# Pan-tilt.net
KiCad netlist of a schematic drawn in Altium Designer
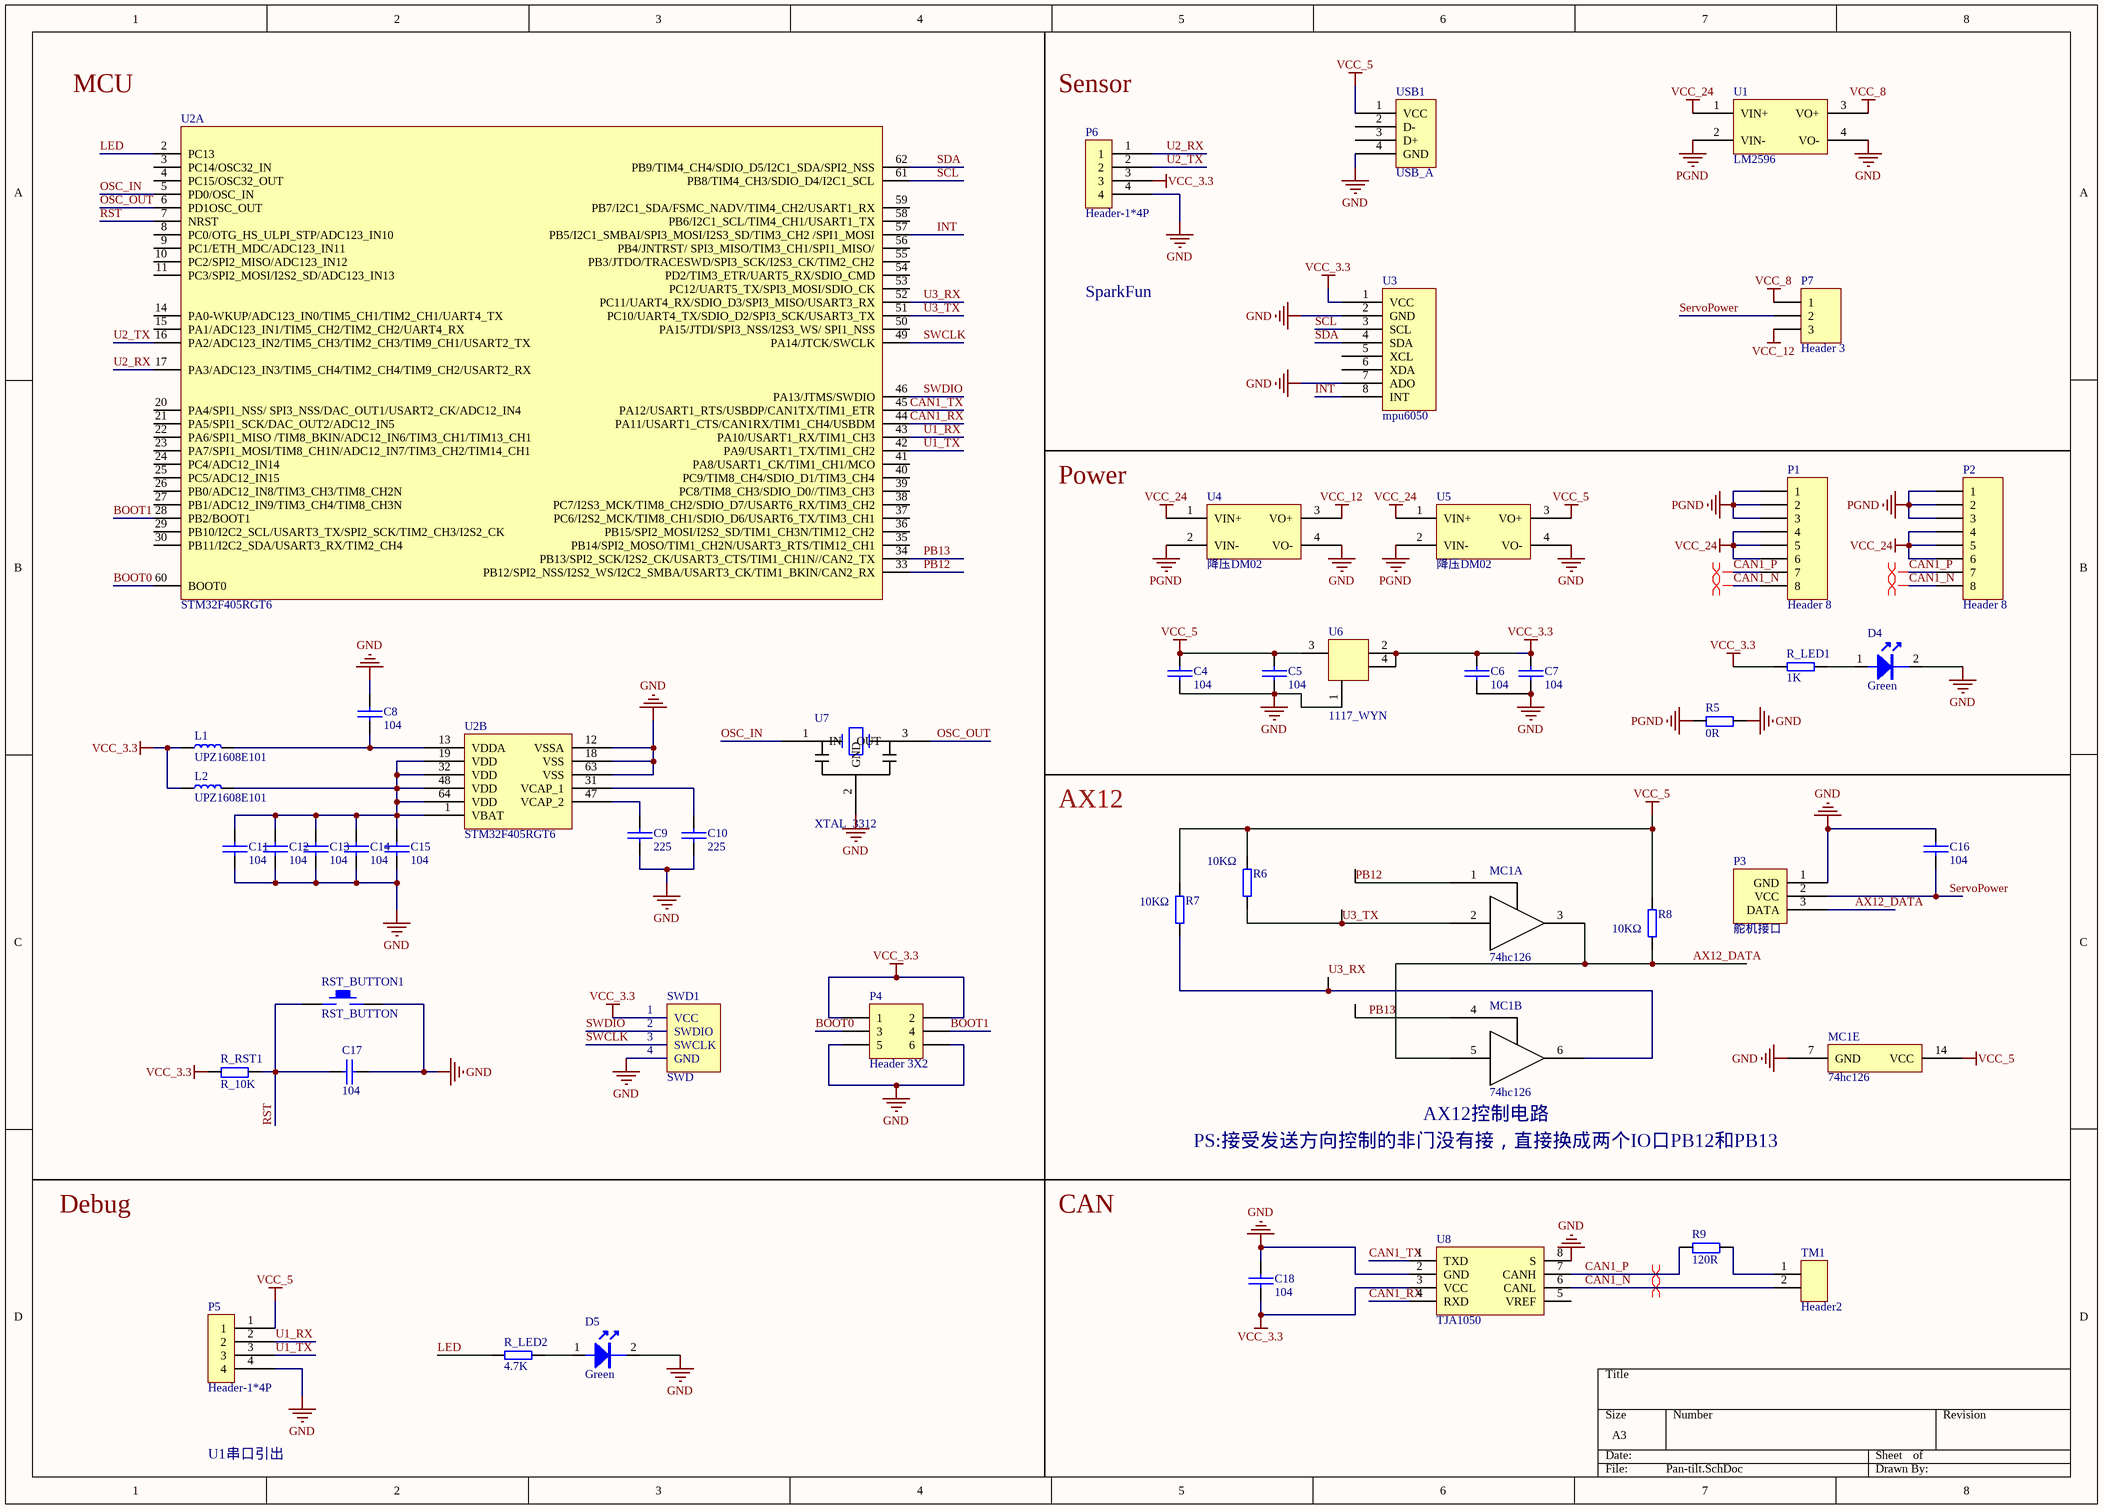
[diagram p0: Pan-tilt.SchDoc]

(export (version "E")
  (design (tool "Eeschema 10.0.6"))
  (components
    (comp (ref "C4") (value "104") (footprint "C0603/1608") (libsource (lib "PCB_Project") (part "CAP_WYN")))
    (comp (ref "C5") (value "104") (footprint "C0603/1608") (libsource (lib "PCB_Project") (part "CAP_WYN")))
    (comp (ref "C6") (value "104") (footprint "C0603/1608") (libsource (lib "PCB_Project") (part "CAP_WYN")))
    (comp (ref "C7") (value "104") (footprint "C0603/1608") (libsource (lib "PCB_Project") (part "CAP_WYN")))
    (comp (ref "C8") (value "104") (footprint "C0603/1608") (libsource (lib "RESCUE2019") (part "Capacitor")))
    (comp (ref "C9") (value "225") (footprint "C0603/1608") (libsource (lib "RESCUE2019") (part "Capacitor")))
    (comp (ref "C10")
      (value "225")
      (footprint "C0603/1608")
      (libsource (lib "RESCUE2019") (part "Capacitor"))
    )
    (comp (ref "C11")
      (value "104")
      (footprint "C0603/1608")
      (libsource (lib "RESCUE2019") (part "Capacitor"))
    )
    (comp (ref "C12")
      (value "104")
      (footprint "C0603/1608")
      (libsource (lib "RESCUE2019") (part "Capacitor"))
    )
    (comp (ref "C13")
      (value "104")
      (footprint "C0603/1608")
      (libsource (lib "RESCUE2019") (part "Capacitor"))
    )
    (comp (ref "C14")
      (value "104")
      (footprint "C0603/1608")
      (libsource (lib "RESCUE2019") (part "Capacitor"))
    )
    (comp (ref "C15")
      (value "104")
      (footprint "C0603/1608")
      (libsource (lib "RESCUE2019") (part "Capacitor"))
    )
    (comp (ref "C16") (value "104") (footprint "C0603/1608") (libsource (lib "PCB_Project") (part "CAP_WYN")))
    (comp (ref "C17")
      (value "104")
      (footprint "C0603/1608")
      (libsource (lib "RESCUE2019") (part "Capacitor"))
    )
    (comp (ref "C18") (value "104") (footprint "C0603/1608") (libsource (lib "PCB_Project") (part "CAP_WYN")))
    (comp (ref "D4")
      (value "LED Green")
      (footprint "LED0603-绿色")
      (fields (field (name "COLOR") "Green"))
      (libsource (lib "PCB_Project") (part "LED"))
    )
    (comp (ref "D5")
      (value "LED Green")
      (footprint "LED0603-绿色")
      (fields (field (name "COLOR") "Green"))
      (libsource (lib "PCB_Project") (part "LED"))
    )
    (comp (ref "L1")
      (value "UPZ1608E101")
      (footprint "L0603/1608")
      (description "贴片磁珠")
      (libsource (lib "RESCUE2019") (part "磁珠"))
    )
    (comp (ref "L2")
      (value "UPZ1608E101")
      (footprint "L0603/1608")
      (description "贴片磁珠")
      (libsource (lib "RESCUE2019") (part "磁珠"))
    )
    (comp (ref "MC1") (value "74hc126") (footprint "SOP-14") (libsource (lib "PCB_Project") (part "74hc126")))
    (comp (ref "P1")
      (value "Header 8")
      (footprint "XH2.54-8P（立式）")
      (description "Header, 8-Pin")
      (fields (field (name "PUBLISHER") "Altium Limited"))
      (libsource (lib "RESCUE2019") (part "Header 8"))
    )
    (comp (ref "P2")
      (value "Header 8")
      (footprint "XH2.54-8P（立式）")
      (description "Header, 8-Pin")
      (fields (field (name "PUBLISHER") "Altium Limited"))
      (libsource (lib "RESCUE2019") (part "Header 8"))
    )
    (comp (ref "P3")
      (value "舵机接口")
      (footprint "5263-3P（立式）")
      (libsource (lib "WMJ2019_Connectors") (part "舵机接口"))
    )
    (comp (ref "P4")
      (value "Header 3X2")
      (footprint "Header-2.54-2*3P（立式）")
      (description "Header, 3-Pin, Dual row")
      (fields (field (name "PUBLISHER") "Altium Limited"))
      (libsource (lib "RESCUE2019") (part "Header 3X2"))
    )
    (comp (ref "P5")
      (value "Header-1*4P")
      (footprint "XH2.54-4P（立式）")
      (description "单排4P排针")
      (libsource (lib "WMJ2019_Connectors") (part "Header-1*4P"))
    )
    (comp (ref "P6")
      (value "Header-1*4P")
      (footprint "XH2.54-4P（立式）")
      (description "单排4P排针")
      (libsource (lib "WMJ2019_Connectors") (part "Header-1*4P"))
    )
    (comp (ref "P7")
      (value "Header 3")
      (footprint "Header-2.54-1*3P（立式）")
      (description "Header, 3-Pin")
      (fields (field (name "PUBLISHER") "Altium Limited"))
      (libsource (lib "RESCUE2019") (part "Header 3"))
    )
    (comp (ref "R5") (value "0R") (footprint "R0603/1608") (libsource (lib "PCB_Project") (part "Resistor")))
    (comp (ref "R6") (value "10KΩ") (footprint "R0603/1608") (libsource (lib "main") (part "RES_WYN")))
    (comp (ref "R7") (value "10KΩ") (footprint "R0603/1608") (libsource (lib "main") (part "RES_WYN")))
    (comp (ref "R8") (value "10KΩ") (footprint "R0603/1608") (libsource (lib "main") (part "RES_WYN")))
    (comp (ref "R9")
      (value "120R")
      (footprint "R0603/1608")
      (libsource (lib "PCB_Project") (part "Resistor"))
    )
    (comp (ref "RST_BUTTON1")
      (value "RST_BUTTON")
      (footprint "SW-PB")
      (libsource (lib "PCB_Project") (part "RST_BUTTON"))
    )
    (comp (ref "R_LED1")
      (value "1K")
      (footprint "R0603/1608")
      (libsource (lib "PCB_Project") (part "RES_WYN"))
    )
    (comp (ref "R_LED2")
      (value "4.7K")
      (footprint "R0603/1608")
      (libsource (lib "PCB_Project") (part "RES_WYN"))
    )
    (comp (ref "R_RST1") (value "R_10K") (footprint "R0603/1608") (libsource (lib "PCB_Project") (part "R")))
    (comp (ref "SWD1") (value "SWD") (footprint "XH2.54-4P（立式）") (libsource (lib "RESCUE2019") (part "SWD")))
    (comp (ref "TM1")
      (value "Header2")
      (footprint "Header-2.54-1*2P（立式）")
      (libsource (lib "PCB_Project") (part "Header2"))
    )
    (comp (ref "U1") (value "LM2596") (footprint "LM2596_big") (libsource (lib "RESCUE2019") (part "降压DM02")))
    (comp (ref "U2")
      (value "STM32F405RGT6")
      (footprint "LQFP64")
      (description "微控制器STM32F405RGT6")
      (libsource (lib "RESCUE2019") (part "STM32F405RGT6"))
    )
    (comp (ref "U3")
      (value "mpu6050")
      (footprint "Header-2.54-1*8P（立式）")
      (libsource (lib "RESCUE2019") (part "mpu6050"))
    )
    (comp (ref "U4") (value "降压DM02") (footprint "DM02") (libsource (lib "PCB_Project") (part "降压DM02")))
    (comp (ref "U5") (value "降压DM02") (footprint "DM02") (libsource (lib "PCB_Project") (part "降压DM02")))
    (comp (ref "U6")
      (value "1117_WYN")
      (footprint "SOT-223")
      (libsource (lib "PCB_Project") (part "1117_WYN"))
    )
    (comp (ref "U7")
      (value "XTAL_3312")
      (footprint "XTAL-3213")
      (libsource (lib "RESCUE2019") (part "XTAL_3312"))
    )
    (comp (ref "U8") (value "TJA1050") (footprint "SOP-8") (libsource (lib "PCB_Project") (part "TJA1050")))
    (comp (ref "USB1")
      (value "USB_A")
      (footprint "USB_A Receptacle - 直插")
      (libsource (lib "RESCUE2019") (part "USB_A"))
    )
  )
  (nets
    (net (code "1") (name "/AX12_DATA") (class "Default")
      (node (ref "MC1") (pin "3") (pintype "passive"))
      (node (ref "MC1") (pin "5") (pintype "passive"))
      (node (ref "P3") (pin "3") (pinfunction "DATA_3") (pintype "passive"))
      (node (ref "R8") (pin "1") (pinfunction "1_1") (pintype "passive"))
    )
    (net (code "2") (name "/BOOT0") (class "Default")
      (node (ref "P4") (pin "3") (pinfunction "3_3") (pintype "passive"))
      (node (ref "U2") (pin "60") (pinfunction "BOOT0_60") (pintype "passive"))
    )
    (net (code "3") (name "/BOOT1") (class "Default")
      (node (ref "P4") (pin "4") (pinfunction "4_4") (pintype "passive"))
      (node (ref "U2") (pin "28") (pinfunction "PB2/BOOT1_28") (pintype "passive"))
    )
    (net (code "4") (name "/CAN1_N") (class "Default")
      (node (ref "P1") (pin "8") (pinfunction "8_8") (pintype "passive"))
      (node (ref "P2") (pin "8") (pinfunction "8_8") (pintype "passive"))
      (node (ref "TM1") (pin "2") (pintype "passive"))
      (node (ref "U8") (pin "6") (pinfunction "CANL_6") (pintype "passive"))
    )
    (net (code "5") (name "/CAN1_P") (class "Default")
      (node (ref "P1") (pin "7") (pinfunction "7_7") (pintype "passive"))
      (node (ref "P2") (pin "7") (pinfunction "7_7") (pintype "passive"))
      (node (ref "R9") (pin "1") (pintype "passive"))
      (node (ref "U8") (pin "7") (pinfunction "CANH_7") (pintype "passive"))
    )
    (net (code "6") (name "/CAN1_RX") (class "Default")
      (node (ref "U2") (pin "44") (pinfunction "PA11/USART1_CTS/CAN1RX/TIM1_CH4/USBDM_44") (pintype "passive"))
      (node (ref "U8") (pin "4") (pinfunction "RXD_4") (pintype "passive"))
    )
    (net (code "7") (name "/CAN1_TX") (class "Default")
      (node (ref "U2") (pin "45") (pinfunction "PA12/USART1_RTS/USBDP/CAN1TX/TIM1_ETR_45") (pintype "passive"))
      (node (ref "U8") (pin "1") (pinfunction "TXD_1") (pintype "passive"))
    )
    (net (code "8") (name "/INT") (class "Default")
      (node (ref "U2") (pin "57") (pinfunction "PB5/I2C1_SMBAI/SPI3_MOSI/I2S3_SD/TIM3_CH2_/SPI1_MOSI_57") (pintype "passive"))
      (node (ref "U3") (pin "8") (pinfunction "INT_8") (pintype "passive"))
    )
    (net (code "9") (name "/LED") (class "Default")
      (node (ref "R_LED2") (pin "1") (pinfunction "1_1") (pintype "passive"))
      (node (ref "U2") (pin "2") (pinfunction "PC13_2") (pintype "passive"))
    )
    (net (code "10") (name "/OSC_IN") (class "Default")
      (node (ref "U2") (pin "5") (pinfunction "PD0/OSC_IN_5") (pintype "passive"))
      (node (ref "U7") (pin "1") (pinfunction "IN_1") (pintype "passive"))
    )
    (net (code "11") (name "/OSC_OUT") (class "Default")
      (node (ref "U2") (pin "6") (pinfunction "PD1OSC_OUT_6") (pintype "passive"))
      (node (ref "U7") (pin "3") (pinfunction "OUT_3") (pintype "passive"))
    )
    (net (code "12") (name "/PB12") (class "Default")
      (node (ref "MC1") (pin "1") (pintype "input"))
      (node (ref "U2") (pin "33") (pinfunction "PB12/SPI2_NSS/I2S2_WS/I2C2_SMBA/USART3_CK/TIM1_BKIN/CAN2_RX_33") (pintype "passive"))
    )
    (net (code "13") (name "/PB13") (class "Default")
      (node (ref "MC1") (pin "4") (pintype "passive"))
      (node (ref "U2") (pin "34") (pinfunction "PB13/SPI2_SCK/I2S2_CK/USART3_CTS/TIM1_CH1N//CAN2_TX_34") (pintype "passive"))
    )
    (net (code "14") (name "/RST") (class "Default")
      (node (ref "C17") (pin "2") (pintype "passive"))
      (node (ref "RST_BUTTON1") (pin "1") (pinfunction "1_1") (pintype "passive"))
      (node (ref "R_RST1") (pin "2") (pintype "passive"))
      (node (ref "U2") (pin "7") (pinfunction "NRST_7") (pintype "passive"))
    )
    (net (code "15") (name "/SCL") (class "Default")
      (node (ref "U2") (pin "61") (pinfunction "PB8/TIM4_CH3/SDIO_D4/I2C1_SCL_61") (pintype "passive"))
      (node (ref "U3") (pin "3") (pinfunction "SCL_3") (pintype "passive"))
    )
    (net (code "16") (name "/SDA") (class "Default")
      (node (ref "U2") (pin "62") (pinfunction "PB9/TIM4_CH4/SDIO_D5/I2C1_SDA/SPI2_NSS_62") (pintype "passive"))
      (node (ref "U3") (pin "4") (pinfunction "SDA_4") (pintype "passive"))
    )
    (net (code "17") (name "/SWCLK") (class "Default")
      (node (ref "SWD1") (pin "3") (pinfunction "SWCLK_3") (pintype "passive"))
      (node (ref "U2") (pin "49") (pinfunction "PA14/JTCK/SWCLK_49") (pintype "passive"))
    )
    (net (code "18") (name "/SWDIO") (class "Default")
      (node (ref "SWD1") (pin "2") (pinfunction "SWDIO_2") (pintype "passive"))
      (node (ref "U2") (pin "46") (pinfunction "PA13/JTMS/SWDIO_46") (pintype "passive"))
    )
    (net (code "19") (name "/ServoPower") (class "Default")
      (node (ref "C16") (pin "2") (pintype "passive"))
      (node (ref "P3") (pin "2") (pinfunction "VCC_2") (pintype "passive"))
      (node (ref "P7") (pin "2") (pinfunction "2_2") (pintype "passive"))
    )
    (net (code "20") (name "/U1_RX") (class "Default")
      (node (ref "P5") (pin "2") (pinfunction "2_2") (pintype "passive"))
      (node (ref "U2") (pin "43") (pinfunction "PA10/USART1_RX/TIM1_CH3_43") (pintype "passive"))
    )
    (net (code "21") (name "/U1_TX") (class "Default")
      (node (ref "P5") (pin "3") (pinfunction "3_3") (pintype "passive"))
      (node (ref "U2") (pin "42") (pinfunction "PA9/USART1_TX/TIM1_CH2_42") (pintype "passive"))
    )
    (net (code "22") (name "/U2_RX") (class "Default")
      (node (ref "P6") (pin "1") (pinfunction "1_1") (pintype "passive"))
      (node (ref "U2") (pin "17") (pinfunction "PA3/ADC123_IN3/TIM5_CH4/TIM2_CH4/TIM9_CH2/USART2_RX_17") (pintype "passive"))
    )
    (net (code "23") (name "/U2_TX") (class "Default")
      (node (ref "P6") (pin "2") (pinfunction "2_2") (pintype "passive"))
      (node (ref "U2") (pin "16") (pinfunction "PA2/ADC123_IN2/TIM5_CH3/TIM2_CH3/TIM9_CH1/USART2_TX_16") (pintype "passive"))
    )
    (net (code "24") (name "/U3_RX") (class "Default")
      (node (ref "MC1") (pin "6") (pintype "passive"))
      (node (ref "R7") (pin "1") (pinfunction "1_1") (pintype "passive"))
      (node (ref "U2") (pin "52") (pinfunction "PC11/UART4_RX/SDIO_D3/SPI3_MISO/USART3_RX_52") (pintype "passive"))
    )
    (net (code "25") (name "/U3_TX") (class "Default")
      (node (ref "MC1") (pin "2") (pintype "input"))
      (node (ref "R6") (pin "1") (pinfunction "1_1") (pintype "passive"))
      (node (ref "U2") (pin "51") (pinfunction "PC10/UART4_TX/SDIO_D2/SPI3_SCK/USART3_TX_51") (pintype "passive"))
    )
    (net (code "26") (name "GND") (class "Default")
      (node (ref "C10") (pin "2") (pintype "passive"))
      (node (ref "C11") (pin "2") (pintype "passive"))
      (node (ref "C12") (pin "2") (pintype "passive"))
      (node (ref "C13") (pin "2") (pintype "passive"))
      (node (ref "C14") (pin "2") (pintype "passive"))
      (node (ref "C15") (pin "2") (pintype "passive"))
      (node (ref "C16") (pin "1") (pintype "passive"))
      (node (ref "C17") (pin "1") (pintype "passive"))
      (node (ref "C18") (pin "1") (pintype "passive"))
      (node (ref "C4") (pin "2") (pintype "passive"))
      (node (ref "C5") (pin "2") (pintype "passive"))
      (node (ref "C6") (pin "2") (pintype "passive"))
      (node (ref "C7") (pin "2") (pintype "passive"))
      (node (ref "C8") (pin "1") (pintype "passive"))
      (node (ref "C9") (pin "2") (pintype "passive"))
      (node (ref "D4") (pin "2") (pinfunction "K_2") (pintype "passive"))
      (node (ref "D5") (pin "2") (pinfunction "K_2") (pintype "passive"))
      (node (ref "MC1") (pin "7") (pinfunction "GND_7") (pintype "passive"))
      (node (ref "P3") (pin "1") (pinfunction "GND_1") (pintype "passive"))
      (node (ref "P4") (pin "5") (pinfunction "5_5") (pintype "passive"))
      (node (ref "P4") (pin "6") (pinfunction "6_6") (pintype "passive"))
      (node (ref "P5") (pin "4") (pinfunction "4_4") (pintype "passive"))
      (node (ref "P6") (pin "4") (pinfunction "4_4") (pintype "passive"))
      (node (ref "R5") (pin "2") (pintype "passive"))
      (node (ref "RST_BUTTON1") (pin "2") (pinfunction "2_2") (pintype "passive"))
      (node (ref "SWD1") (pin "4") (pinfunction "GND_4") (pintype "passive"))
      (node (ref "U1") (pin "4") (pinfunction "VO-_4") (pintype "passive"))
      (node (ref "U2") (pin "12") (pinfunction "VSSA_12") (pintype "passive"))
      (node (ref "U2") (pin "18") (pinfunction "VSS_18") (pintype "passive"))
      (node (ref "U2") (pin "63") (pinfunction "VSS_63") (pintype "passive"))
      (node (ref "U3") (pin "2") (pinfunction "GND_2") (pintype "passive"))
      (node (ref "U3") (pin "7") (pinfunction "ADO_7") (pintype "passive"))
      (node (ref "U4") (pin "4") (pinfunction "VO-_4") (pintype "passive"))
      (node (ref "U5") (pin "4") (pinfunction "VO-_4") (pintype "passive"))
      (node (ref "U6") (pin "1") (pintype "passive"))
      (node (ref "U7") (pin "2") (pinfunction "GND_2") (pintype "passive"))
      (node (ref "U8") (pin "2") (pinfunction "GND_2") (pintype "passive"))
      (node (ref "U8") (pin "8") (pinfunction "S_8") (pintype "passive"))
      (node (ref "USB1") (pin "4") (pinfunction "GND_4") (pintype "passive"))
    )
    (net (code "27") (name "Net-(D4-A)") (class "Default")
      (node (ref "D4") (pin "1") (pinfunction "A_1") (pintype "passive"))
      (node (ref "R_LED1") (pin "2") (pinfunction "2_2") (pintype "passive"))
    )
    (net (code "28") (name "Net-(D5-A)") (class "Default")
      (node (ref "D5") (pin "1") (pinfunction "A_1") (pintype "passive"))
      (node (ref "R_LED2") (pin "2") (pinfunction "2_2") (pintype "passive"))
    )
    (net (code "29") (name "Net-(R9-Pad2)") (class "Default")
      (node (ref "R9") (pin "2") (pintype "passive"))
      (node (ref "TM1") (pin "1") (pintype "passive"))
    )
    (net (code "30") (name "Net-(U2B-VBAT)") (class "Default")
      (node (ref "C11") (pin "1") (pintype "passive"))
      (node (ref "C12") (pin "1") (pintype "passive"))
      (node (ref "C13") (pin "1") (pintype "passive"))
      (node (ref "C14") (pin "1") (pintype "passive"))
      (node (ref "C15") (pin "1") (pintype "passive"))
      (node (ref "L2") (pin "2") (pinfunction "2_2") (pintype "passive"))
      (node (ref "U2") (pin "1") (pinfunction "VBAT_1") (pintype "passive"))
      (node (ref "U2") (pin "19") (pinfunction "VDD_19") (pintype "passive"))
      (node (ref "U2") (pin "32") (pinfunction "VDD_32") (pintype "passive"))
      (node (ref "U2") (pin "48") (pinfunction "VDD_48") (pintype "passive"))
      (node (ref "U2") (pin "64") (pinfunction "VDD_64") (pintype "passive"))
    )
    (net (code "31") (name "Net-(U2B-VCAP_1)") (class "Default")
      (node (ref "C10") (pin "1") (pintype "passive"))
      (node (ref "U2") (pin "31") (pinfunction "VCAP_1_31") (pintype "passive"))
    )
    (net (code "32") (name "Net-(U2B-VCAP_2)") (class "Default")
      (node (ref "C9") (pin "1") (pintype "passive"))
      (node (ref "U2") (pin "47") (pinfunction "VCAP_2_47") (pintype "passive"))
    )
    (net (code "33") (name "Net-(U2B-VDDA)") (class "Default")
      (node (ref "C8") (pin "2") (pintype "passive"))
      (node (ref "L1") (pin "2") (pinfunction "2_2") (pintype "passive"))
      (node (ref "U2") (pin "13") (pinfunction "VDDA_13") (pintype "passive"))
    )
    (net (code "34") (name "PGND") (class "Default")
      (node (ref "P1") (pin "1") (pinfunction "1_1") (pintype "passive"))
      (node (ref "P1") (pin "2") (pinfunction "2_2") (pintype "passive"))
      (node (ref "P1") (pin "3") (pinfunction "3_3") (pintype "passive"))
      (node (ref "P2") (pin "1") (pinfunction "1_1") (pintype "passive"))
      (node (ref "P2") (pin "2") (pinfunction "2_2") (pintype "passive"))
      (node (ref "P2") (pin "3") (pinfunction "3_3") (pintype "passive"))
      (node (ref "R5") (pin "1") (pintype "passive"))
      (node (ref "U1") (pin "2") (pinfunction "VIN-_2") (pintype "passive"))
      (node (ref "U4") (pin "2") (pinfunction "VIN-_2") (pintype "passive"))
      (node (ref "U5") (pin "2") (pinfunction "VIN-_2") (pintype "passive"))
    )
    (net (code "35") (name "VCC_3.3") (class "Default")
      (node (ref "C18") (pin "2") (pintype "passive"))
      (node (ref "C6") (pin "1") (pintype "passive"))
      (node (ref "C7") (pin "1") (pintype "passive"))
      (node (ref "L1") (pin "1") (pinfunction "1_1") (pintype "passive"))
      (node (ref "L2") (pin "1") (pinfunction "1_1") (pintype "passive"))
      (node (ref "P4") (pin "1") (pinfunction "1_1") (pintype "passive"))
      (node (ref "P4") (pin "2") (pinfunction "2_2") (pintype "passive"))
      (node (ref "P6") (pin "3") (pinfunction "3_3") (pintype "passive"))
      (node (ref "R_LED1") (pin "1") (pinfunction "1_1") (pintype "passive"))
      (node (ref "R_RST1") (pin "1") (pintype "passive"))
      (node (ref "SWD1") (pin "1") (pinfunction "VCC_1") (pintype "passive"))
      (node (ref "U3") (pin "1") (pinfunction "VCC_1") (pintype "passive"))
      (node (ref "U6") (pin "2") (pintype "passive"))
      (node (ref "U6") (pin "4") (pintype "passive"))
      (node (ref "U8") (pin "3") (pinfunction "VCC_3") (pintype "passive"))
    )
    (net (code "36") (name "VCC_5") (class "Default")
      (node (ref "C4") (pin "1") (pintype "passive"))
      (node (ref "C5") (pin "1") (pintype "passive"))
      (node (ref "MC1") (pin "14") (pinfunction "VCC_14") (pintype "passive"))
      (node (ref "P5") (pin "1") (pinfunction "1_1") (pintype "passive"))
      (node (ref "R6") (pin "2") (pinfunction "2_2") (pintype "passive"))
      (node (ref "R7") (pin "2") (pinfunction "2_2") (pintype "passive"))
      (node (ref "R8") (pin "2") (pinfunction "2_2") (pintype "passive"))
      (node (ref "U5") (pin "3") (pinfunction "VO+_3") (pintype "passive"))
      (node (ref "U6") (pin "3") (pintype "passive"))
      (node (ref "USB1") (pin "1") (pinfunction "VCC_1") (pintype "passive"))
    )
    (net (code "37") (name "VCC_8") (class "Default")
      (node (ref "P7") (pin "1") (pinfunction "1_1") (pintype "passive"))
      (node (ref "U1") (pin "3") (pinfunction "VO+_3") (pintype "passive"))
    )
    (net (code "38") (name "VCC_12") (class "Default")
      (node (ref "P7") (pin "3") (pinfunction "3_3") (pintype "passive"))
      (node (ref "U4") (pin "3") (pinfunction "VO+_3") (pintype "passive"))
    )
    (net (code "39") (name "VCC_24") (class "Default")
      (node (ref "P1") (pin "4") (pinfunction "4_4") (pintype "passive"))
      (node (ref "P1") (pin "5") (pinfunction "5_5") (pintype "passive"))
      (node (ref "P1") (pin "6") (pinfunction "6_6") (pintype "passive"))
      (node (ref "P2") (pin "4") (pinfunction "4_4") (pintype "passive"))
      (node (ref "P2") (pin "5") (pinfunction "5_5") (pintype "passive"))
      (node (ref "P2") (pin "6") (pinfunction "6_6") (pintype "passive"))
      (node (ref "U1") (pin "1") (pinfunction "VIN+_1") (pintype "passive"))
      (node (ref "U4") (pin "1") (pinfunction "VIN+_1") (pintype "passive"))
      (node (ref "U5") (pin "1") (pinfunction "VIN+_1") (pintype "passive"))
    )
    (net (code "40") (name "unconnected-(U2A-PA0-WKUP{slash}ADC123_IN0{slash}TIM5_CH1{slash}TIM2_CH1{slash}UART4_TX-Pad14)") (class "Default")
      (node (ref "U2") (pin "14") (pinfunction "PA0-WKUP/ADC123_IN0/TIM5_CH1/TIM2_CH1/UART4_TX_14") (pintype "passive"))
    )
    (net (code "41") (name "unconnected-(U2A-PA1{slash}ADC123_IN1{slash}TIM5_CH2{slash}TIM2_CH2{slash}UART4_RX-Pad15)") (class "Default")
      (node (ref "U2") (pin "15") (pinfunction "PA1/ADC123_IN1/TIM5_CH2/TIM2_CH2/UART4_RX_15") (pintype "passive"))
    )
    (net (code "42") (name "unconnected-(U2A-PA4{slash}SPI1_NSS{slash}_SPI3_NSS{slash}DAC_OUT1{slash}USART2_CK{slash}ADC12_IN4-Pad20)") (class "Default")
      (node (ref "U2") (pin "20") (pinfunction "PA4/SPI1_NSS/_SPI3_NSS/DAC_OUT1/USART2_CK/ADC12_IN4_20") (pintype "passive"))
    )
    (net (code "43") (name "unconnected-(U2A-PA5{slash}SPI1_SCK{slash}DAC_OUT2{slash}ADC12_IN5-Pad21)") (class "Default")
      (node (ref "U2") (pin "21") (pinfunction "PA5/SPI1_SCK/DAC_OUT2/ADC12_IN5_21") (pintype "passive"))
    )
    (net (code "44") (name "unconnected-(U2A-PA6{slash}SPI1_MISO_{slash}TIM8_BKIN{slash}ADC12_IN6{slash}TIM3_CH1{slash}TIM13_CH1-Pad22)") (class "Default")
      (node (ref "U2") (pin "22") (pinfunction "PA6/SPI1_MISO_/TIM8_BKIN/ADC12_IN6/TIM3_CH1/TIM13_CH1_22") (pintype "passive"))
    )
    (net (code "45") (name "unconnected-(U2A-PA7{slash}SPI1_MOSI{slash}TIM8_CH1N{slash}ADC12_IN7{slash}TIM3_CH2{slash}TIM14_CH1-Pad23)") (class "Default")
      (node (ref "U2") (pin "23") (pinfunction "PA7/SPI1_MOSI/TIM8_CH1N/ADC12_IN7/TIM3_CH2/TIM14_CH1_23") (pintype "passive"))
    )
    (net (code "46") (name "unconnected-(U2A-PA8{slash}USART1_CK{slash}TIM1_CH1{slash}MCO-Pad41)") (class "Default")
      (node (ref "U2") (pin "41") (pinfunction "PA8/USART1_CK/TIM1_CH1/MCO_41") (pintype "passive"))
    )
    (net (code "47") (name "unconnected-(U2A-PA15{slash}JTDI{slash}SPI3_NSS{slash}I2S3_WS{slash}_SPI1_NSS-Pad50)") (class "Default")
      (node (ref "U2") (pin "50") (pinfunction "PA15/JTDI/SPI3_NSS/I2S3_WS/_SPI1_NSS_50") (pintype "passive"))
    )
    (net (code "48") (name "unconnected-(U2A-PB0{slash}ADC12_IN8{slash}TIM3_CH3{slash}TIM8_CH2N-Pad26)") (class "Default")
      (node (ref "U2") (pin "26") (pinfunction "PB0/ADC12_IN8/TIM3_CH3/TIM8_CH2N_26") (pintype "passive"))
    )
    (net (code "49") (name "unconnected-(U2A-PB1{slash}ADC12_IN9{slash}TIM3_CH4{slash}TIM8_CH3N-Pad27)") (class "Default")
      (node (ref "U2") (pin "27") (pinfunction "PB1/ADC12_IN9/TIM3_CH4/TIM8_CH3N_27") (pintype "passive"))
    )
    (net (code "50") (name "unconnected-(U2A-PB3{slash}JTDO{slash}TRACESWD{slash}SPI3_SCK{slash}I2S3_CK{slash}TIM2_CH2-Pad55)") (class "Default")
      (node (ref "U2") (pin "55") (pinfunction "PB3/JTDO/TRACESWD/SPI3_SCK/I2S3_CK/TIM2_CH2_55") (pintype "passive"))
    )
    (net (code "51") (name "unconnected-(U2A-PB4{slash}JNTRST{slash}_SPI3_MISO{slash}TIM3_CH1{slash}SPI1_MISO{slash}-Pad56)") (class "Default")
      (node (ref "U2") (pin "56") (pinfunction "PB4/JNTRST/_SPI3_MISO/TIM3_CH1/SPI1_MISO/_56") (pintype "passive"))
    )
    (net (code "52") (name "unconnected-(U2A-PB6{slash}I2C1_SCL{slash}TIM4_CH1{slash}USART1_TX-Pad58)") (class "Default")
      (node (ref "U2") (pin "58") (pinfunction "PB6/I2C1_SCL/TIM4_CH1/USART1_TX_58") (pintype "passive"))
    )
    (net (code "53") (name "unconnected-(U2A-PB7{slash}I2C1_SDA{slash}FSMC_NADV{slash}TIM4_CH2{slash}USART1_RX-Pad59)") (class "Default")
      (node (ref "U2") (pin "59") (pinfunction "PB7/I2C1_SDA/FSMC_NADV/TIM4_CH2/USART1_RX_59") (pintype "passive"))
    )
    (net (code "54") (name "unconnected-(U2A-PB10{slash}I2C2_SCL{slash}USART3_TX{slash}SPI2_SCK{slash}TIM2_CH3{slash}I2S2_CK-Pad29)") (class "Default")
      (node (ref "U2") (pin "29") (pinfunction "PB10/I2C2_SCL/USART3_TX/SPI2_SCK/TIM2_CH3/I2S2_CK_29") (pintype "passive"))
    )
    (net (code "55") (name "unconnected-(U2A-PB11{slash}I2C2_SDA{slash}USART3_RX{slash}TIM2_CH4-Pad30)") (class "Default")
      (node (ref "U2") (pin "30") (pinfunction "PB11/I2C2_SDA/USART3_RX/TIM2_CH4_30") (pintype "passive"))
    )
    (net (code "56") (name "unconnected-(U2A-PB14{slash}SPI2_MOSO{slash}TIM1_CH2N{slash}USART3_RTS{slash}TIM12_CH1-Pad35)") (class "Default")
      (node (ref "U2") (pin "35") (pinfunction "PB14/SPI2_MOSO/TIM1_CH2N/USART3_RTS/TIM12_CH1_35") (pintype "passive"))
    )
    (net (code "57") (name "unconnected-(U2A-PB15{slash}SPI2_MOSI{slash}I2S2_SD{slash}TIM1_CH3N{slash}TIM12_CH2-Pad36)") (class "Default")
      (node (ref "U2") (pin "36") (pinfunction "PB15/SPI2_MOSI/I2S2_SD/TIM1_CH3N/TIM12_CH2_36") (pintype "passive"))
    )
    (net (code "58") (name "unconnected-(U2A-PC0{slash}OTG_HS_ULPI_STP{slash}ADC123_IN10-Pad8)") (class "Default")
      (node (ref "U2") (pin "8") (pinfunction "PC0/OTG_HS_ULPI_STP/ADC123_IN10_8") (pintype "passive"))
    )
    (net (code "59") (name "unconnected-(U2A-PC1{slash}ETH_MDC{slash}ADC123_IN11-Pad9)") (class "Default")
      (node (ref "U2") (pin "9") (pinfunction "PC1/ETH_MDC/ADC123_IN11_9") (pintype "passive"))
    )
    (net (code "60") (name "unconnected-(U2A-PC2{slash}SPI2_MISO{slash}ADC123_IN12-Pad10)") (class "Default")
      (node (ref "U2") (pin "10") (pinfunction "PC2/SPI2_MISO/ADC123_IN12_10") (pintype "passive"))
    )
    (net (code "61") (name "unconnected-(U2A-PC3{slash}SPI2_MOSI{slash}I2S2_SD{slash}ADC123_IN13-Pad11)") (class "Default")
      (node (ref "U2") (pin "11") (pinfunction "PC3/SPI2_MOSI/I2S2_SD/ADC123_IN13_11") (pintype "passive"))
    )
    (net (code "62") (name "unconnected-(U2A-PC4{slash}ADC12_IN14-Pad24)") (class "Default")
      (node (ref "U2") (pin "24") (pinfunction "PC4/ADC12_IN14_24") (pintype "passive"))
    )
    (net (code "63") (name "unconnected-(U2A-PC5{slash}ADC12_IN15-Pad25)") (class "Default")
      (node (ref "U2") (pin "25") (pinfunction "PC5/ADC12_IN15_25") (pintype "passive"))
    )
    (net (code "64") (name "unconnected-(U2A-PC6{slash}I2S2_MCK{slash}TIM8_CH1{slash}SDIO_D6{slash}USART6_TX{slash}TIM3_CH1-Pad37)") (class "Default")
      (node (ref "U2") (pin "37") (pinfunction "PC6/I2S2_MCK/TIM8_CH1/SDIO_D6/USART6_TX/TIM3_CH1_37") (pintype "passive"))
    )
    (net (code "65") (name "unconnected-(U2A-PC7{slash}I2S3_MCK{slash}TIM8_CH2{slash}SDIO_D7{slash}USART6_RX{slash}TIM3_CH2-Pad38)") (class "Default")
      (node (ref "U2") (pin "38") (pinfunction "PC7/I2S3_MCK/TIM8_CH2/SDIO_D7/USART6_RX/TIM3_CH2_38") (pintype "passive"))
    )
    (net (code "66") (name "unconnected-(U2A-PC8{slash}TIM8_CH3{slash}SDIO_D0{slash}{slash}TIM3_CH3-Pad39)") (class "Default")
      (node (ref "U2") (pin "39") (pinfunction "PC8/TIM8_CH3/SDIO_D0//TIM3_CH3_39") (pintype "passive"))
    )
    (net (code "67") (name "unconnected-(U2A-PC9{slash}TIM8_CH4{slash}SDIO_D1{slash}TIM3_CH4-Pad40)") (class "Default")
      (node (ref "U2") (pin "40") (pinfunction "PC9/TIM8_CH4/SDIO_D1/TIM3_CH4_40") (pintype "passive"))
    )
    (net (code "68") (name "unconnected-(U2A-PC12{slash}UART5_TX{slash}SPI3_MOSI{slash}SDIO_CK-Pad53)") (class "Default")
      (node (ref "U2") (pin "53") (pinfunction "PC12/UART5_TX/SPI3_MOSI/SDIO_CK_53") (pintype "passive"))
    )
    (net (code "69") (name "unconnected-(U2A-PC14{slash}OSC32_IN-Pad3)") (class "Default")
      (node (ref "U2") (pin "3") (pinfunction "PC14/OSC32_IN_3") (pintype "passive"))
    )
    (net (code "70") (name "unconnected-(U2A-PC15{slash}OSC32_OUT-Pad4)") (class "Default")
      (node (ref "U2") (pin "4") (pinfunction "PC15/OSC32_OUT_4") (pintype "passive"))
    )
    (net (code "71") (name "unconnected-(U2A-PD2{slash}TIM3_ETR{slash}UART5_RX{slash}SDIO_CMD-Pad54)") (class "Default")
      (node (ref "U2") (pin "54") (pinfunction "PD2/TIM3_ETR/UART5_RX/SDIO_CMD_54") (pintype "passive"))
    )
    (net (code "72") (name "unconnected-(U3-XCL-Pad5)") (class "Default")
      (node (ref "U3") (pin "5") (pinfunction "XCL_5") (pintype "passive"))
    )
    (net (code "73") (name "unconnected-(U3-XDA-Pad6)") (class "Default")
      (node (ref "U3") (pin "6") (pinfunction "XDA_6") (pintype "passive"))
    )
    (net (code "74") (name "unconnected-(U8-VREF-Pad5)") (class "Default")
      (node (ref "U8") (pin "5") (pinfunction "VREF_5") (pintype "passive"))
    )
    (net (code "75") (name "unconnected-(USB1-D+-Pad3)") (class "Default")
      (node (ref "USB1") (pin "3") (pinfunction "D+_3") (pintype "passive"))
    )
    (net (code "76") (name "unconnected-(USB1-D--Pad2)") (class "Default")
      (node (ref "USB1") (pin "2") (pinfunction "D-_2") (pintype "passive"))
    )
  )
)
